# Zirkulation.net
KiCad netlist of a schematic drawn in EAGLE
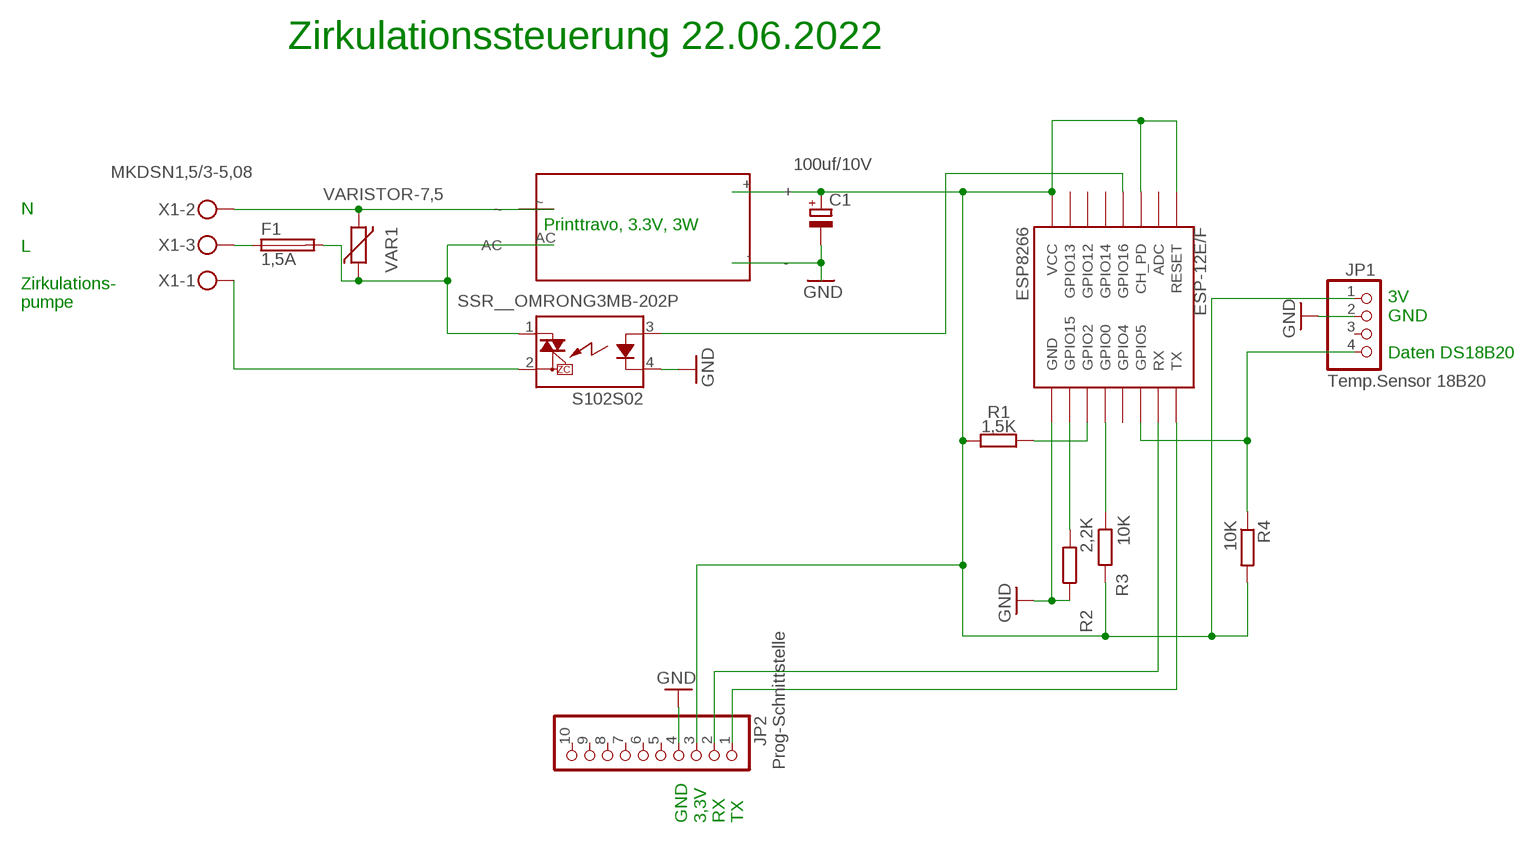
[diagram p0: schematic, sheet 1]

(export (version "E")
  (design (tool "Eeschema 10.0.6"))
  (components
    (comp (ref "C1")
      (value "100uf/10V")
      (footprint "eagle-import:E2,5-7")
      (libsource (lib "eagle-import") (part "CPOL-EUE2.5-7"))
    )
    (comp (ref "ESP-12E/F")
      (value "ESP8266")
      (footprint "eagle-import:ESP12-SMD")
      (libsource (lib "eagle-import") (part "ESP12SMD"))
    )
    (comp (ref "F1")
      (value "1,5A")
      (footprint "eagle-import:LITTLEFUSE")
      (libsource (lib "eagle-import") (part "LITTLEFUSE"))
    )
    (comp (ref "JP1")
      (value "Temp.Sensor 18B20")
      (footprint "eagle-import:1X04")
      (libsource (lib "eagle-import") (part "PINHD-1X4"))
    )
    (comp (ref "JP2")
      (value "Prog-Schnittstelle")
      (footprint "eagle-import:1X10")
      (libsource (lib "eagle-import") (part "PINHD-1X10"))
    )
    (comp (ref "PRINTTRAFO3.3V,_3W")
      (value "PRINTTRAFO")
      (footprint "eagle-import:PRINTTRAFO")
      (libsource (lib "eagle-import") (part "PRINTTRAFO"))
    )
    (comp (ref "R1")
      (value "1,5K")
      (footprint "eagle-import:0204_7")
      (libsource (lib "eagle-import") (part "R-EU_0204/7"))
    )
    (comp (ref "R2")
      (value "2,2K")
      (footprint "eagle-import:0204_7")
      (libsource (lib "eagle-import") (part "R-EU_0204/7"))
    )
    (comp (ref "R3")
      (value "10K")
      (footprint "eagle-import:0204_7")
      (libsource (lib "eagle-import") (part "R-EU_0204/7"))
    )
    (comp (ref "R4")
      (value "10K")
      (footprint "eagle-import:0204_7")
      (libsource (lib "eagle-import") (part "R-EU_0204/7"))
    )
    (comp (ref "SSR__OMRONG3MB-202P")
      (value "S102S02")
      (footprint "eagle-import:S202S02")
      (libsource (lib "eagle-import") (part "S02S021"))
    )
    (comp (ref "VAR1")
      (value "VARISTOR-7,5")
      (footprint "eagle-import:R-7,5")
      (libsource (lib "eagle-import") (part "VARISTOR-7,5"))
    )
    (comp (ref "X1")
      (value "MKDSN1,5/3-5,08")
      (footprint "eagle-import:MKDSN1,5_3-5,08")
      (libsource (lib "eagle-import") (part "MKDSN1,5/3-5,08"))
    )
  )
  (nets
    (net (code "1") (name "GND") (class "Default")
      (node (ref "C1") (pin "-") (pinfunction "-_-") (pintype "passive"))
      (node (ref "ESP-12E/F") (pin "GND") (pinfunction "GND_GND") (pintype "bidirectional"))
      (node (ref "JP1") (pin "2") (pinfunction "2_2") (pintype "passive"))
      (node (ref "JP2") (pin "4") (pinfunction "4_4") (pintype "passive"))
      (node (ref "PRINTTRAFO3.3V,_3W") (pin "-") (pinfunction "-_-") (pintype "bidirectional"))
      (node (ref "R2") (pin "1") (pinfunction "1_1") (pintype "passive"))
      (node (ref "SSR__OMRONG3MB-202P") (pin "4") (pinfunction "K_4") (pintype "passive"))
    )
    (net (code "2") (name "Net-(C1-Pad+)") (class "Default")
      (node (ref "C1") (pin "+") (pinfunction "+_+") (pintype "passive"))
      (node (ref "ESP-12E/F") (pin "CH_PD") (pinfunction "CH_PD_CH_PD") (pintype "bidirectional"))
      (node (ref "ESP-12E/F") (pin "RESET") (pinfunction "RESET_RESET") (pintype "bidirectional"))
      (node (ref "ESP-12E/F") (pin "VCC") (pinfunction "VCC_VCC") (pintype "bidirectional"))
      (node (ref "JP1") (pin "1") (pinfunction "1_1") (pintype "passive"))
      (node (ref "JP2") (pin "3") (pinfunction "3_3") (pintype "passive"))
      (node (ref "PRINTTRAFO3.3V,_3W") (pin "+") (pinfunction "+_+") (pintype "bidirectional"))
      (node (ref "R1") (pin "2") (pinfunction "2_2") (pintype "passive"))
      (node (ref "R3") (pin "2") (pinfunction "2_2") (pintype "passive"))
      (node (ref "R4") (pin "2") (pinfunction "2_2") (pintype "passive"))
    )
    (net (code "3") (name "Net-(ESP-12E/F-GPIO5)") (class "Default")
      (node (ref "ESP-12E/F") (pin "GPIO4") (pinfunction "GPIO5_GPIO4") (pintype "bidirectional"))
      (node (ref "JP1") (pin "4") (pinfunction "4_4") (pintype "passive"))
      (node (ref "R4") (pin "1") (pinfunction "1_1") (pintype "passive"))
    )
    (net (code "4") (name "Net-(ESP-12E/F-PadGPIO0)") (class "Default")
      (node (ref "ESP-12E/F") (pin "GPIO0") (pinfunction "GPIO0_GPIO0") (pintype "bidirectional"))
      (node (ref "R3") (pin "1") (pinfunction "1_1") (pintype "passive"))
    )
    (net (code "5") (name "Net-(ESP-12E/F-PadGPIO2)") (class "Default")
      (node (ref "ESP-12E/F") (pin "GPIO2") (pinfunction "GPIO2_GPIO2") (pintype "bidirectional"))
      (node (ref "R1") (pin "1") (pinfunction "1_1") (pintype "passive"))
    )
    (net (code "6") (name "Net-(ESP-12E/F-PadGPIO15)") (class "Default")
      (node (ref "ESP-12E/F") (pin "GPIO15") (pinfunction "GPIO15_GPIO15") (pintype "bidirectional"))
      (node (ref "R2") (pin "2") (pinfunction "2_2") (pintype "passive"))
    )
    (net (code "7") (name "Net-(ESP-12E/F-RX)") (class "Default")
      (node (ref "ESP-12E/F") (pin "RXD0") (pinfunction "RX_RXD0") (pintype "bidirectional"))
      (node (ref "JP2") (pin "2") (pinfunction "2_2") (pintype "passive"))
    )
    (net (code "8") (name "Net-(ESP-12E/F-TX)") (class "Default")
      (node (ref "ESP-12E/F") (pin "TXD0") (pinfunction "TX_TXD0") (pintype "bidirectional"))
      (node (ref "JP2") (pin "1") (pinfunction "1_1") (pintype "passive"))
    )
    (net (code "9") (name "Net-(SSR__OMRONG3MB-202P-A)") (class "Default")
      (node (ref "ESP-12E/F") (pin "GPIO16") (pinfunction "GPIO16_GPIO16") (pintype "bidirectional"))
      (node (ref "SSR__OMRONG3MB-202P") (pin "3") (pinfunction "A_3") (pintype "passive"))
    )
    (net (code "10") (name "Net-(SSR__OMRONG3MB-202P-DS1)") (class "Default")
      (node (ref "F1") (pin "2") (pinfunction "2_2") (pintype "passive"))
      (node (ref "PRINTTRAFO3.3V,_3W") (pin "AC") (pinfunction "AC_AC") (pintype "bidirectional"))
      (node (ref "SSR__OMRONG3MB-202P") (pin "1") (pinfunction "DS1_1") (pintype "passive"))
      (node (ref "VAR1") (pin "1") (pinfunction "1_1") (pintype "passive"))
    )
    (net (code "11") (name "Net-(SSR__OMRONG3MB-202P-DS2)") (class "Default")
      (node (ref "SSR__OMRONG3MB-202P") (pin "2") (pinfunction "DS2_2") (pintype "passive"))
      (node (ref "X1") (pin "1") (pinfunction "KL_1") (pintype "passive"))
    )
    (net (code "12") (name "Net-(X1B-KL)") (class "Default")
      (node (ref "PRINTTRAFO3.3V,_3W") (pin "~") (pinfunction "~_~") (pintype "bidirectional"))
      (node (ref "VAR1") (pin "2") (pinfunction "2_2") (pintype "passive"))
      (node (ref "X1") (pin "2") (pinfunction "KL_2") (pintype "passive"))
    )
    (net (code "13") (name "Net-(X1C-KL)") (class "Default")
      (node (ref "F1") (pin "1") (pinfunction "1_1") (pintype "passive"))
      (node (ref "X1") (pin "3") (pinfunction "KL_3") (pintype "passive"))
    )
    (net (code "14") (name "unconnected-(ESP-12E/F-GPIO4-PadGPIO5)") (class "Default")
      (node (ref "ESP-12E/F") (pin "GPIO5") (pinfunction "GPIO4_GPIO5") (pintype "bidirectional"))
    )
    (net (code "15") (name "unconnected-(ESP-12E/F-PadADC)") (class "Default")
      (node (ref "ESP-12E/F") (pin "ADC") (pinfunction "ADC_ADC") (pintype "bidirectional"))
    )
    (net (code "16") (name "unconnected-(ESP-12E/F-PadGPIO12)") (class "Default")
      (node (ref "ESP-12E/F") (pin "GPIO12") (pinfunction "GPIO12_GPIO12") (pintype "bidirectional"))
    )
    (net (code "17") (name "unconnected-(ESP-12E/F-PadGPIO13)") (class "Default")
      (node (ref "ESP-12E/F") (pin "GPIO13") (pinfunction "GPIO13_GPIO13") (pintype "bidirectional"))
    )
    (net (code "18") (name "unconnected-(ESP-12E/F-PadGPIO14)") (class "Default")
      (node (ref "ESP-12E/F") (pin "GPIO14") (pinfunction "GPIO14_GPIO14") (pintype "bidirectional"))
    )
    (net (code "19") (name "unconnected-(JP1-Pad3)") (class "Default")
      (node (ref "JP1") (pin "3") (pinfunction "3_3") (pintype "passive"))
    )
    (net (code "20") (name "unconnected-(JP2-Pad5)") (class "Default")
      (node (ref "JP2") (pin "5") (pinfunction "5_5") (pintype "passive"))
    )
    (net (code "21") (name "unconnected-(JP2-Pad6)") (class "Default")
      (node (ref "JP2") (pin "6") (pinfunction "6_6") (pintype "passive"))
    )
    (net (code "22") (name "unconnected-(JP2-Pad7)") (class "Default")
      (node (ref "JP2") (pin "7") (pinfunction "7_7") (pintype "passive"))
    )
    (net (code "23") (name "unconnected-(JP2-Pad8)") (class "Default")
      (node (ref "JP2") (pin "8") (pinfunction "8_8") (pintype "passive"))
    )
    (net (code "24") (name "unconnected-(JP2-Pad9)") (class "Default")
      (node (ref "JP2") (pin "9") (pinfunction "9_9") (pintype "passive"))
    )
    (net (code "25") (name "unconnected-(JP2-Pad10)") (class "Default")
      (node (ref "JP2") (pin "10") (pinfunction "10_10") (pintype "passive"))
    )
  )
)
